# Chua.net
KiCad netlist of a schematic drawn in EAGLE
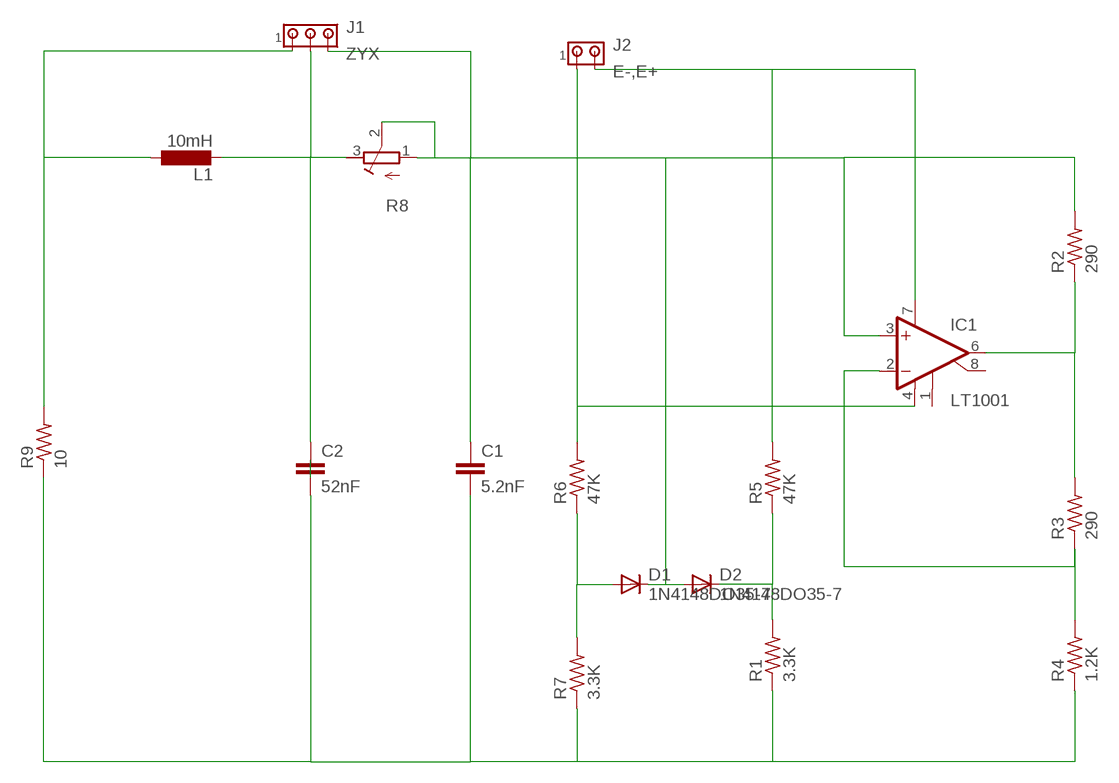
[diagram p0: schematic, sheet 1]

(export (version "E")
  (design (tool "Eeschema 10.0.6"))
  (components
    (comp (ref "C1")
      (value "5.2nF")
      (footprint "eagle-import:C025-060X050")
      (libsource (lib "eagle-import") (part "C-EU025-060X050"))
    )
    (comp (ref "C2")
      (value "52nF")
      (footprint "eagle-import:C025-060X050")
      (libsource (lib "eagle-import") (part "C-EU025-060X050"))
    )
    (comp (ref "D1")
      (value "1N4148DO35-7")
      (footprint "eagle-import:DO35-7")
      (libsource (lib "eagle-import") (part "1N4148DO35-7"))
    )
    (comp (ref "D2")
      (value "1N4148DO35-7")
      (footprint "eagle-import:DO35-7")
      (libsource (lib "eagle-import") (part "1N4148DO35-7"))
    )
    (comp (ref "IC1")
      (value "LT1001")
      (footprint "eagle-import:DIL08")
      (libsource (lib "eagle-import") (part "LT1001N"))
    )
    (comp (ref "J1")
      (value "ZYX")
      (footprint "eagle-import:10X03MTA")
      (libsource (lib "eagle-import") (part "MTA03-100"))
    )
    (comp (ref "J2")
      (value "E-,E+")
      (footprint "eagle-import:10X02MTA")
      (libsource (lib "eagle-import") (part "MTA02-100"))
    )
    (comp (ref "L1")
      (value "10mH")
      (footprint "eagle-import:0207_5V")
      (libsource (lib "eagle-import") (part "L-EU0207/5V"))
    )
    (comp (ref "R1")
      (value "3.3K")
      (footprint "eagle-import:0204_7")
      (libsource (lib "eagle-import") (part "R-US_0204/7"))
    )
    (comp (ref "R2")
      (value "290")
      (footprint "eagle-import:0204_7")
      (libsource (lib "eagle-import") (part "R-US_0204/7"))
    )
    (comp (ref "R3")
      (value "290")
      (footprint "eagle-import:0204_7")
      (libsource (lib "eagle-import") (part "R-US_0204/7"))
    )
    (comp (ref "R4")
      (value "1.2K")
      (footprint "eagle-import:0204_7")
      (libsource (lib "eagle-import") (part "R-US_0204/7"))
    )
    (comp (ref "R5")
      (value "47K")
      (footprint "eagle-import:0204_7")
      (libsource (lib "eagle-import") (part "R-US_0204/7"))
    )
    (comp (ref "R6")
      (value "47K")
      (footprint "eagle-import:0204_7")
      (libsource (lib "eagle-import") (part "R-US_0204/7"))
    )
    (comp (ref "R7")
      (value "3.3K")
      (footprint "eagle-import:0204_7")
      (libsource (lib "eagle-import") (part "R-US_0204/7"))
    )
    (comp (ref "R8")
      (value "R-TRIMM3296Y")
      (footprint "eagle-import:RTRIM3296Y")
      (libsource (lib "eagle-import") (part "R-TRIMM3296Y"))
    )
    (comp (ref "R9")
      (value "10")
      (footprint "eagle-import:0204_7")
      (libsource (lib "eagle-import") (part "R-US_0204/7"))
    )
  )
  (nets
    (net (code "1") (name "Net-(C1-Pad2)") (class "Default")
      (node (ref "C1") (pin "2") (pinfunction "2_2") (pintype "passive"))
      (node (ref "C2") (pin "2") (pinfunction "2_2") (pintype "passive"))
      (node (ref "R1") (pin "1") (pinfunction "1_1") (pintype "passive"))
      (node (ref "R4") (pin "1") (pinfunction "1_1") (pintype "passive"))
      (node (ref "R7") (pin "1") (pinfunction "1_1") (pintype "passive"))
      (node (ref "R9") (pin "1") (pinfunction "1_1") (pintype "passive"))
    )
    (net (code "2") (name "Net-(D1-PadA)") (class "Default")
      (node (ref "D1") (pin "A") (pinfunction "A_A") (pintype "passive"))
      (node (ref "R6") (pin "1") (pinfunction "1_1") (pintype "passive"))
      (node (ref "R7") (pin "2") (pinfunction "2_2") (pintype "passive"))
    )
    (net (code "3") (name "Net-(D2-PadC)") (class "Default")
      (node (ref "D2") (pin "C") (pinfunction "C_C") (pintype "passive"))
      (node (ref "R1") (pin "2") (pinfunction "2_2") (pintype "passive"))
      (node (ref "R5") (pin "1") (pinfunction "1_1") (pintype "passive"))
    )
    (net (code "4") (name "Net-(IC1-+IN)") (class "Default")
      (node (ref "C1") (pin "1") (pinfunction "1_1") (pintype "passive"))
      (node (ref "D1") (pin "C") (pinfunction "C_C") (pintype "passive"))
      (node (ref "D2") (pin "A") (pinfunction "A_A") (pintype "passive"))
      (node (ref "IC1") (pin "3") (pinfunction "+IN_3") (pintype "input"))
      (node (ref "J1") (pin "3") (pinfunction "3_3") (pintype "passive"))
      (node (ref "R2") (pin "2") (pinfunction "2_2") (pintype "passive"))
      (node (ref "R8") (pin "1") (pinfunction "E_1") (pintype "passive"))
      (node (ref "R8") (pin "2") (pinfunction "S_2") (pintype "passive"))
    )
    (net (code "5") (name "Net-(IC1--IN)") (class "Default")
      (node (ref "IC1") (pin "2") (pinfunction "-IN_2") (pintype "input"))
      (node (ref "R3") (pin "1") (pinfunction "1_1") (pintype "passive"))
      (node (ref "R4") (pin "2") (pinfunction "2_2") (pintype "passive"))
    )
    (net (code "6") (name "Net-(IC1-OUT)") (class "Default")
      (node (ref "IC1") (pin "6") (pinfunction "OUT_6") (pintype "output"))
      (node (ref "R2") (pin "1") (pinfunction "1_1") (pintype "passive"))
      (node (ref "R3") (pin "2") (pinfunction "2_2") (pintype "passive"))
    )
    (net (code "7") (name "Net-(IC1-V+)") (class "Default")
      (node (ref "IC1") (pin "7") (pinfunction "V+_7") (pintype "power_in"))
      (node (ref "J2") (pin "2") (pinfunction "2_2") (pintype "passive"))
      (node (ref "R5") (pin "2") (pinfunction "2_2") (pintype "passive"))
    )
    (net (code "8") (name "Net-(IC1-V-)") (class "Default")
      (node (ref "IC1") (pin "4") (pinfunction "V-_4") (pintype "power_in"))
      (node (ref "J2") (pin "1") (pinfunction "1_1") (pintype "passive"))
      (node (ref "R6") (pin "2") (pinfunction "2_2") (pintype "passive"))
    )
    (net (code "9") (name "Net-(J1-Pad1)") (class "Default")
      (node (ref "J1") (pin "1") (pinfunction "1_1") (pintype "passive"))
      (node (ref "L1") (pin "1") (pinfunction "1_1") (pintype "passive"))
      (node (ref "R9") (pin "2") (pinfunction "2_2") (pintype "passive"))
    )
    (net (code "10") (name "Net-(R8-A)") (class "Default")
      (node (ref "C2") (pin "1") (pinfunction "1_1") (pintype "passive"))
      (node (ref "J1") (pin "2") (pinfunction "2_2") (pintype "passive"))
      (node (ref "L1") (pin "2") (pinfunction "2_2") (pintype "passive"))
      (node (ref "R8") (pin "3") (pinfunction "A_3") (pintype "passive"))
    )
    (net (code "11") (name "unconnected-(IC1-CMP1-Pad1)") (class "Default")
      (node (ref "IC1") (pin "1") (pinfunction "CMP1_1") (pintype "passive"))
    )
    (net (code "12") (name "unconnected-(IC1-CMP2-Pad8)") (class "Default")
      (node (ref "IC1") (pin "8") (pinfunction "CMP2_8") (pintype "passive"))
    )
  )
)
